# M002A.net
KiCad netlist of a schematic drawn in EAGLE
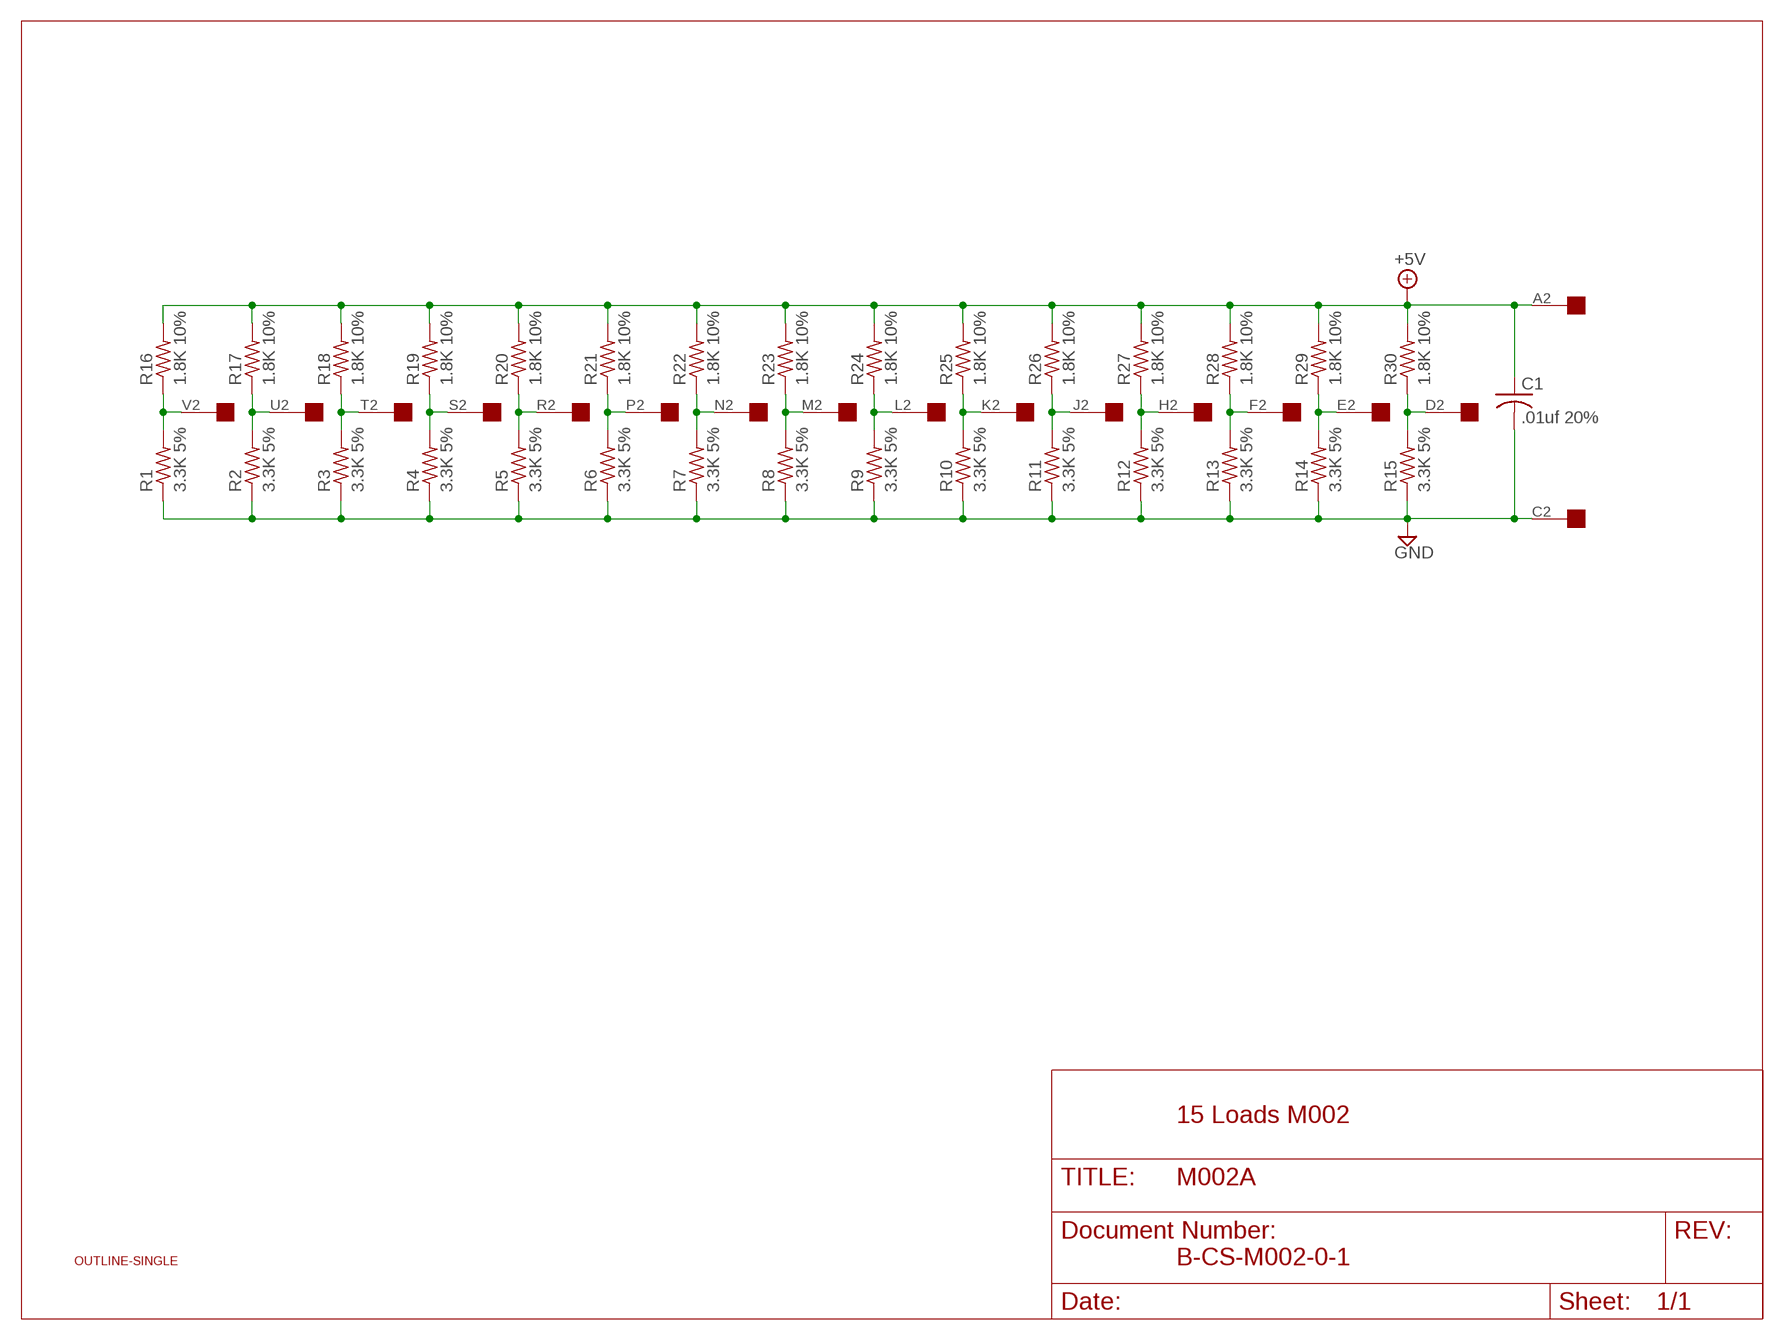
[diagram p0: schematic, sheet 1]

(export (version "E")
  (design (tool "Eeschema 10.0.6"))
  (components
    (comp (ref "C1")
      (value ".01uf 20%")
      (footprint "eagle-import:C050-025X075")
      (libsource (lib "eagle-import") (part "C-US050-025X075"))
    )
    (comp (ref "R1")
      (value "3.3K 5%")
      (footprint "eagle-import:0207_10")
      (libsource (lib "eagle-import") (part "R-US_0207/10"))
    )
    (comp (ref "R2")
      (value "3.3K 5%")
      (footprint "eagle-import:0207_10")
      (libsource (lib "eagle-import") (part "R-US_0207/10"))
    )
    (comp (ref "R3")
      (value "3.3K 5%")
      (footprint "eagle-import:0207_10")
      (libsource (lib "eagle-import") (part "R-US_0207/10"))
    )
    (comp (ref "R4")
      (value "3.3K 5%")
      (footprint "eagle-import:0207_10")
      (libsource (lib "eagle-import") (part "R-US_0207/10"))
    )
    (comp (ref "R5")
      (value "3.3K 5%")
      (footprint "eagle-import:0207_10")
      (libsource (lib "eagle-import") (part "R-US_0207/10"))
    )
    (comp (ref "R6")
      (value "3.3K 5%")
      (footprint "eagle-import:0207_10")
      (libsource (lib "eagle-import") (part "R-US_0207/10"))
    )
    (comp (ref "R7")
      (value "3.3K 5%")
      (footprint "eagle-import:0207_10")
      (libsource (lib "eagle-import") (part "R-US_0207/10"))
    )
    (comp (ref "R8")
      (value "3.3K 5%")
      (footprint "eagle-import:0207_10")
      (libsource (lib "eagle-import") (part "R-US_0207/10"))
    )
    (comp (ref "R9")
      (value "3.3K 5%")
      (footprint "eagle-import:0207_10")
      (libsource (lib "eagle-import") (part "R-US_0207/10"))
    )
    (comp (ref "R10")
      (value "3.3K 5%")
      (footprint "eagle-import:0207_10")
      (libsource (lib "eagle-import") (part "R-US_0207/10"))
    )
    (comp (ref "R11")
      (value "3.3K 5%")
      (footprint "eagle-import:0207_10")
      (libsource (lib "eagle-import") (part "R-US_0207/10"))
    )
    (comp (ref "R12")
      (value "3.3K 5%")
      (footprint "eagle-import:0207_10")
      (libsource (lib "eagle-import") (part "R-US_0207/10"))
    )
    (comp (ref "R13")
      (value "3.3K 5%")
      (footprint "eagle-import:0207_10")
      (libsource (lib "eagle-import") (part "R-US_0207/10"))
    )
    (comp (ref "R14")
      (value "3.3K 5%")
      (footprint "eagle-import:0207_10")
      (libsource (lib "eagle-import") (part "R-US_0207/10"))
    )
    (comp (ref "R15")
      (value "3.3K 5%")
      (footprint "eagle-import:0207_10")
      (libsource (lib "eagle-import") (part "R-US_0207/10"))
    )
    (comp (ref "R16")
      (value "1.8K 10%")
      (footprint "eagle-import:0207_10")
      (libsource (lib "eagle-import") (part "R-US_0207/10"))
    )
    (comp (ref "R17")
      (value "1.8K 10%")
      (footprint "eagle-import:0207_10")
      (libsource (lib "eagle-import") (part "R-US_0207/10"))
    )
    (comp (ref "R18")
      (value "1.8K 10%")
      (footprint "eagle-import:0207_10")
      (libsource (lib "eagle-import") (part "R-US_0207/10"))
    )
    (comp (ref "R19")
      (value "1.8K 10%")
      (footprint "eagle-import:0207_10")
      (libsource (lib "eagle-import") (part "R-US_0207/10"))
    )
    (comp (ref "R20")
      (value "1.8K 10%")
      (footprint "eagle-import:0207_10")
      (libsource (lib "eagle-import") (part "R-US_0207/10"))
    )
    (comp (ref "R21")
      (value "1.8K 10%")
      (footprint "eagle-import:0207_10")
      (libsource (lib "eagle-import") (part "R-US_0207/10"))
    )
    (comp (ref "R22")
      (value "1.8K 10%")
      (footprint "eagle-import:0207_10")
      (libsource (lib "eagle-import") (part "R-US_0207/10"))
    )
    (comp (ref "R23")
      (value "1.8K 10%")
      (footprint "eagle-import:0207_10")
      (libsource (lib "eagle-import") (part "R-US_0207/10"))
    )
    (comp (ref "R24")
      (value "1.8K 10%")
      (footprint "eagle-import:0207_10")
      (libsource (lib "eagle-import") (part "R-US_0207/10"))
    )
    (comp (ref "R25")
      (value "1.8K 10%")
      (footprint "eagle-import:0207_10")
      (libsource (lib "eagle-import") (part "R-US_0207/10"))
    )
    (comp (ref "R26")
      (value "1.8K 10%")
      (footprint "eagle-import:0207_10")
      (libsource (lib "eagle-import") (part "R-US_0207/10"))
    )
    (comp (ref "R27")
      (value "1.8K 10%")
      (footprint "eagle-import:0207_10")
      (libsource (lib "eagle-import") (part "R-US_0207/10"))
    )
    (comp (ref "R28")
      (value "1.8K 10%")
      (footprint "eagle-import:0207_10")
      (libsource (lib "eagle-import") (part "R-US_0207/10"))
    )
    (comp (ref "R29")
      (value "1.8K 10%")
      (footprint "eagle-import:0207_10")
      (libsource (lib "eagle-import") (part "R-US_0207/10"))
    )
    (comp (ref "R30")
      (value "1.8K 10%")
      (footprint "eagle-import:0207_10")
      (libsource (lib "eagle-import") (part "R-US_0207/10"))
    )
    (comp (ref "U$1")
      (value "OUTLINE-SINGLE")
      (footprint "eagle-import:SINGLE")
      (libsource (lib "eagle-import") (part "OUTLINE-SINGLE"))
    )
    (comp (ref "U$2")
      (value "EDGE-1")
      (footprint "eagle-import:EDGE-CON1")
      (libsource (lib "eagle-import") (part "EDGE-1"))
    )
  )
  (nets
    (net (code "1") (name "+5V") (class "Default")
      (node (ref "C1") (pin "1") (pinfunction "1_1") (pintype "passive"))
      (node (ref "R16") (pin "2") (pinfunction "2_2") (pintype "passive"))
      (node (ref "R17") (pin "2") (pinfunction "2_2") (pintype "passive"))
      (node (ref "R18") (pin "2") (pinfunction "2_2") (pintype "passive"))
      (node (ref "R19") (pin "2") (pinfunction "2_2") (pintype "passive"))
      (node (ref "R20") (pin "2") (pinfunction "2_2") (pintype "passive"))
      (node (ref "R21") (pin "2") (pinfunction "2_2") (pintype "passive"))
      (node (ref "R22") (pin "2") (pinfunction "2_2") (pintype "passive"))
      (node (ref "R23") (pin "2") (pinfunction "2_2") (pintype "passive"))
      (node (ref "R24") (pin "2") (pinfunction "2_2") (pintype "passive"))
      (node (ref "R25") (pin "2") (pinfunction "2_2") (pintype "passive"))
      (node (ref "R26") (pin "2") (pinfunction "2_2") (pintype "passive"))
      (node (ref "R27") (pin "2") (pinfunction "2_2") (pintype "passive"))
      (node (ref "R28") (pin "2") (pinfunction "2_2") (pintype "passive"))
      (node (ref "R29") (pin "2") (pinfunction "2_2") (pintype "passive"))
      (node (ref "R30") (pin "2") (pinfunction "2_2") (pintype "passive"))
      (node (ref "U$2") (pin "A2") (pinfunction "1_A2") (pintype "bidirectional"))
    )
    (net (code "2") (name "GND") (class "Default")
      (node (ref "C1") (pin "2") (pinfunction "2_2") (pintype "passive"))
      (node (ref "R1") (pin "1") (pinfunction "1_1") (pintype "passive"))
      (node (ref "R10") (pin "1") (pinfunction "1_1") (pintype "passive"))
      (node (ref "R11") (pin "1") (pinfunction "1_1") (pintype "passive"))
      (node (ref "R12") (pin "1") (pinfunction "1_1") (pintype "passive"))
      (node (ref "R13") (pin "1") (pinfunction "1_1") (pintype "passive"))
      (node (ref "R14") (pin "1") (pinfunction "1_1") (pintype "passive"))
      (node (ref "R15") (pin "1") (pinfunction "1_1") (pintype "passive"))
      (node (ref "R2") (pin "1") (pinfunction "1_1") (pintype "passive"))
      (node (ref "R3") (pin "1") (pinfunction "1_1") (pintype "passive"))
      (node (ref "R4") (pin "1") (pinfunction "1_1") (pintype "passive"))
      (node (ref "R5") (pin "1") (pinfunction "1_1") (pintype "passive"))
      (node (ref "R6") (pin "1") (pinfunction "1_1") (pintype "passive"))
      (node (ref "R7") (pin "1") (pinfunction "1_1") (pintype "passive"))
      (node (ref "R8") (pin "1") (pinfunction "1_1") (pintype "passive"))
      (node (ref "R9") (pin "1") (pinfunction "1_1") (pintype "passive"))
      (node (ref "U$2") (pin "C2") (pinfunction "1_C2") (pintype "bidirectional"))
    )
    (net (code "3") (name "Net-(U$2D-1)") (class "Default")
      (node (ref "R15") (pin "2") (pinfunction "2_2") (pintype "passive"))
      (node (ref "R30") (pin "1") (pinfunction "1_1") (pintype "passive"))
      (node (ref "U$2") (pin "D2") (pinfunction "1_D2") (pintype "bidirectional"))
    )
    (net (code "4") (name "Net-(U$2E-1)") (class "Default")
      (node (ref "R14") (pin "2") (pinfunction "2_2") (pintype "passive"))
      (node (ref "R29") (pin "1") (pinfunction "1_1") (pintype "passive"))
      (node (ref "U$2") (pin "E2") (pinfunction "1_E2") (pintype "bidirectional"))
    )
    (net (code "5") (name "Net-(U$2F-1)") (class "Default")
      (node (ref "R13") (pin "2") (pinfunction "2_2") (pintype "passive"))
      (node (ref "R28") (pin "1") (pinfunction "1_1") (pintype "passive"))
      (node (ref "U$2") (pin "F2") (pinfunction "1_F2") (pintype "bidirectional"))
    )
    (net (code "6") (name "Net-(U$2G-1)") (class "Default")
      (node (ref "R12") (pin "2") (pinfunction "2_2") (pintype "passive"))
      (node (ref "R27") (pin "1") (pinfunction "1_1") (pintype "passive"))
      (node (ref "U$2") (pin "H2") (pinfunction "1_H2") (pintype "bidirectional"))
    )
    (net (code "7") (name "Net-(U$2H-1)") (class "Default")
      (node (ref "R11") (pin "2") (pinfunction "2_2") (pintype "passive"))
      (node (ref "R26") (pin "1") (pinfunction "1_1") (pintype "passive"))
      (node (ref "U$2") (pin "J2") (pinfunction "1_J2") (pintype "bidirectional"))
    )
    (net (code "8") (name "Net-(U$2I-1)") (class "Default")
      (node (ref "R10") (pin "2") (pinfunction "2_2") (pintype "passive"))
      (node (ref "R25") (pin "1") (pinfunction "1_1") (pintype "passive"))
      (node (ref "U$2") (pin "K2") (pinfunction "1_K2") (pintype "bidirectional"))
    )
    (net (code "9") (name "Net-(U$2J-1)") (class "Default")
      (node (ref "R24") (pin "1") (pinfunction "1_1") (pintype "passive"))
      (node (ref "R9") (pin "2") (pinfunction "2_2") (pintype "passive"))
      (node (ref "U$2") (pin "L2") (pinfunction "1_L2") (pintype "bidirectional"))
    )
    (net (code "10") (name "Net-(U$2K-1)") (class "Default")
      (node (ref "R23") (pin "1") (pinfunction "1_1") (pintype "passive"))
      (node (ref "R8") (pin "2") (pinfunction "2_2") (pintype "passive"))
      (node (ref "U$2") (pin "M2") (pinfunction "1_M2") (pintype "bidirectional"))
    )
    (net (code "11") (name "Net-(U$2L-1)") (class "Default")
      (node (ref "R22") (pin "1") (pinfunction "1_1") (pintype "passive"))
      (node (ref "R7") (pin "2") (pinfunction "2_2") (pintype "passive"))
      (node (ref "U$2") (pin "N2") (pinfunction "1_N2") (pintype "bidirectional"))
    )
    (net (code "12") (name "Net-(U$2M-1)") (class "Default")
      (node (ref "R21") (pin "1") (pinfunction "1_1") (pintype "passive"))
      (node (ref "R6") (pin "2") (pinfunction "2_2") (pintype "passive"))
      (node (ref "U$2") (pin "P2") (pinfunction "1_P2") (pintype "bidirectional"))
    )
    (net (code "13") (name "Net-(U$2N-1)") (class "Default")
      (node (ref "R20") (pin "1") (pinfunction "1_1") (pintype "passive"))
      (node (ref "R5") (pin "2") (pinfunction "2_2") (pintype "passive"))
      (node (ref "U$2") (pin "R2") (pinfunction "1_R2") (pintype "bidirectional"))
    )
    (net (code "14") (name "Net-(U$2O-1)") (class "Default")
      (node (ref "R19") (pin "1") (pinfunction "1_1") (pintype "passive"))
      (node (ref "R4") (pin "2") (pinfunction "2_2") (pintype "passive"))
      (node (ref "U$2") (pin "S2") (pinfunction "1_S2") (pintype "bidirectional"))
    )
    (net (code "15") (name "Net-(U$2P-1)") (class "Default")
      (node (ref "R18") (pin "1") (pinfunction "1_1") (pintype "passive"))
      (node (ref "R3") (pin "2") (pinfunction "2_2") (pintype "passive"))
      (node (ref "U$2") (pin "T2") (pinfunction "1_T2") (pintype "bidirectional"))
    )
    (net (code "16") (name "Net-(U$2Q-1)") (class "Default")
      (node (ref "R17") (pin "1") (pinfunction "1_1") (pintype "passive"))
      (node (ref "R2") (pin "2") (pinfunction "2_2") (pintype "passive"))
      (node (ref "U$2") (pin "U2") (pinfunction "1_U2") (pintype "bidirectional"))
    )
    (net (code "17") (name "Net-(U$2R-1)") (class "Default")
      (node (ref "R1") (pin "2") (pinfunction "2_2") (pintype "passive"))
      (node (ref "R16") (pin "1") (pinfunction "1_1") (pintype "passive"))
      (node (ref "U$2") (pin "V2") (pinfunction "1_V2") (pintype "bidirectional"))
    )
  )
)
